# PLL.net
KiCad netlist of a schematic drawn in Altium Designer
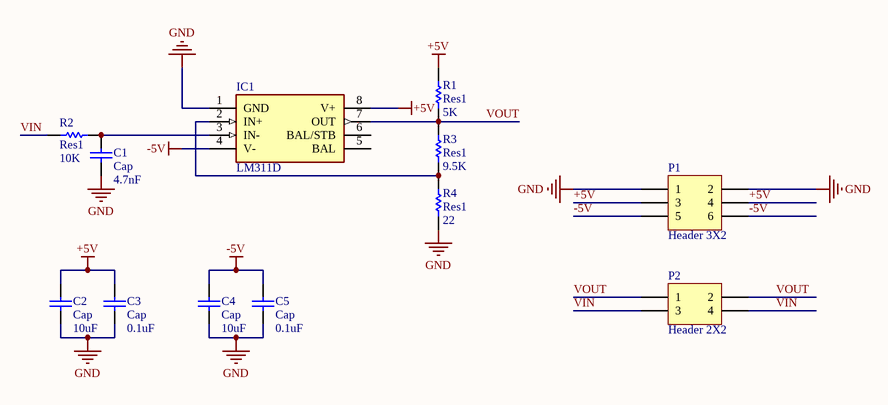
[diagram p0: PLL.SchDoc]

(export (version "E")
  (design (tool "Eeschema 10.0.6"))
  (components
    (comp (ref "C1")
      (value "Cap")
      (footprint "1608[0603]")
      (description "Capacitor")
      (fields (field (name "ALTIUM_VALUE") "4.7nF") (field (name "PUBLISHER") "Altium Limited"))
      (libsource (lib "Miscellaneous Devices") (part "Cap"))
    )
    (comp (ref "C2")
      (value "Cap")
      (footprint "1608[0603]")
      (description "Capacitor")
      (fields (field (name "ALTIUM_VALUE") "10uF") (field (name "PUBLISHER") "Altium Limited"))
      (libsource (lib "Miscellaneous Devices") (part "Cap"))
    )
    (comp (ref "C3")
      (value "Cap")
      (footprint "1608[0603]")
      (description "Capacitor")
      (fields (field (name "ALTIUM_VALUE") "0.1uF") (field (name "PUBLISHER") "Altium Limited"))
      (libsource (lib "Miscellaneous Devices") (part "Cap"))
    )
    (comp (ref "C4")
      (value "Cap")
      (footprint "1608[0603]")
      (description "Capacitor")
      (fields (field (name "ALTIUM_VALUE") "10uF") (field (name "PUBLISHER") "Altium Limited"))
      (libsource (lib "Miscellaneous Devices") (part "Cap"))
    )
    (comp (ref "C5")
      (value "Cap")
      (footprint "1608[0603]")
      (description "Capacitor")
      (fields (field (name "ALTIUM_VALUE") "0.1uF") (field (name "PUBLISHER") "Altium Limited"))
      (libsource (lib "Miscellaneous Devices") (part "Cap"))
    )
    (comp (ref "IC1")
      (value "LM311D")
      (footprint "SamacSys:SOIC127P600X175-8N")
      (description "Integrated Circuit")
      (fields (field (name "MOUSER PART NUMBER") "511-LM311D") (field (name "RS PART NUMBER") "1686808"))
      (libsource (lib "*") (part "LM311D"))
    )
    (comp (ref "P1")
      (value "Header 3X2")
      (footprint "HDR2X3")
      (description "Header, 3-Pin, Dual row")
      (fields (field (name "PUBLISHER") "Altium Limited"))
      (libsource (lib "Miscellaneous Connectors") (part "Header 3X2"))
    )
    (comp (ref "P2")
      (value "Header 2X2")
      (footprint "HDR2X2")
      (description "Header, 2-Pin, Dual row")
      (fields (field (name "PUBLISHER") "Altium Limited"))
      (libsource (lib "Miscellaneous Connectors") (part "Header 2X2"))
    )
    (comp (ref "R1")
      (value "Res1")
      (footprint "J1-0603")
      (description "Resistor")
      (fields (field (name "ALTIUM_VALUE") "5K") (field (name "PUBLISHER") "Altium Limited"))
      (libsource (lib "Miscellaneous Devices") (part "Res1"))
    )
    (comp (ref "R2")
      (value "Res1")
      (footprint "J1-0603")
      (description "Resistor")
      (fields (field (name "ALTIUM_VALUE") "10K") (field (name "PUBLISHER") "Altium Limited"))
      (libsource (lib "Miscellaneous Devices") (part "Res1"))
    )
    (comp (ref "R3")
      (value "Res1")
      (footprint "J1-0603")
      (description "Resistor")
      (fields (field (name "ALTIUM_VALUE") "9.5K") (field (name "PUBLISHER") "Altium Limited"))
      (libsource (lib "Miscellaneous Devices") (part "Res1"))
    )
    (comp (ref "R4")
      (value "Res1")
      (footprint "J1-0603")
      (description "Resistor")
      (fields (field (name "ALTIUM_VALUE") "22") (field (name "PUBLISHER") "Altium Limited"))
      (libsource (lib "Miscellaneous Devices") (part "Res1"))
    )
  )
  (nets
    (net (code "1") (name "+5V") (class "Default")
      (node (ref "C2") (pin "2") (pinfunction "2_2") (pintype "passive"))
      (node (ref "C3") (pin "2") (pinfunction "2_2") (pintype "passive"))
      (node (ref "IC1") (pin "8") (pinfunction "V+_8") (pintype "passive"))
      (node (ref "P1") (pin "3") (pinfunction "3_3") (pintype "passive"))
      (node (ref "P1") (pin "4") (pinfunction "4_4") (pintype "passive"))
      (node (ref "R1") (pin "2") (pinfunction "2_2") (pintype "passive"))
    )
    (net (code "2") (name "-5V") (class "Default")
      (node (ref "C4") (pin "2") (pinfunction "2_2") (pintype "passive"))
      (node (ref "C5") (pin "2") (pinfunction "2_2") (pintype "passive"))
      (node (ref "IC1") (pin "4") (pinfunction "V-_4") (pintype "passive"))
      (node (ref "P1") (pin "5") (pinfunction "5_5") (pintype "passive"))
      (node (ref "P1") (pin "6") (pinfunction "6_6") (pintype "passive"))
    )
    (net (code "3") (name "/VIN") (class "Default")
      (node (ref "P2") (pin "3") (pinfunction "3_3") (pintype "passive"))
      (node (ref "P2") (pin "4") (pinfunction "4_4") (pintype "passive"))
      (node (ref "R2") (pin "2") (pinfunction "2_2") (pintype "passive"))
    )
    (net (code "4") (name "/VOUT") (class "Default")
      (node (ref "IC1") (pin "7") (pinfunction "OUT_7") (pintype "output"))
      (node (ref "P2") (pin "1") (pinfunction "1_1") (pintype "passive"))
      (node (ref "P2") (pin "2") (pinfunction "2_2") (pintype "passive"))
      (node (ref "R1") (pin "1") (pinfunction "1_1") (pintype "passive"))
      (node (ref "R3") (pin "2") (pinfunction "2_2") (pintype "passive"))
    )
    (net (code "5") (name "GND") (class "Default")
      (node (ref "C1") (pin "1") (pinfunction "1_1") (pintype "passive"))
      (node (ref "C2") (pin "1") (pinfunction "1_1") (pintype "passive"))
      (node (ref "C3") (pin "1") (pinfunction "1_1") (pintype "passive"))
      (node (ref "C4") (pin "1") (pinfunction "1_1") (pintype "passive"))
      (node (ref "C5") (pin "1") (pinfunction "1_1") (pintype "passive"))
      (node (ref "IC1") (pin "1") (pinfunction "GND_1") (pintype "power_in"))
      (node (ref "P1") (pin "1") (pinfunction "1_1") (pintype "passive"))
      (node (ref "P1") (pin "2") (pinfunction "2_2") (pintype "passive"))
      (node (ref "R4") (pin "1") (pinfunction "1_1") (pintype "passive"))
    )
    (net (code "6") (name "Net-(IC1-IN+)") (class "Default")
      (node (ref "IC1") (pin "2") (pinfunction "IN+_2") (pintype "input"))
      (node (ref "R3") (pin "1") (pinfunction "1_1") (pintype "passive"))
      (node (ref "R4") (pin "2") (pinfunction "2_2") (pintype "passive"))
    )
    (net (code "7") (name "Net-(IC1-IN-)") (class "Default")
      (node (ref "C1") (pin "2") (pinfunction "2_2") (pintype "passive"))
      (node (ref "IC1") (pin "3") (pinfunction "IN-_3") (pintype "input"))
      (node (ref "R2") (pin "1") (pinfunction "1_1") (pintype "passive"))
    )
    (net (code "8") (name "unconnected-(IC1-BAL-Pad5)") (class "Default")
      (node (ref "IC1") (pin "5") (pinfunction "BAL_5") (pintype "passive"))
    )
    (net (code "9") (name "unconnected-(IC1-BAL{slash}STB-Pad6)") (class "Default")
      (node (ref "IC1") (pin "6") (pinfunction "BAL/STB_6") (pintype "passive"))
    )
  )
)
